# Data_Conversion_BottomBoard.net
KiCad netlist of a schematic drawn in Altium Designer
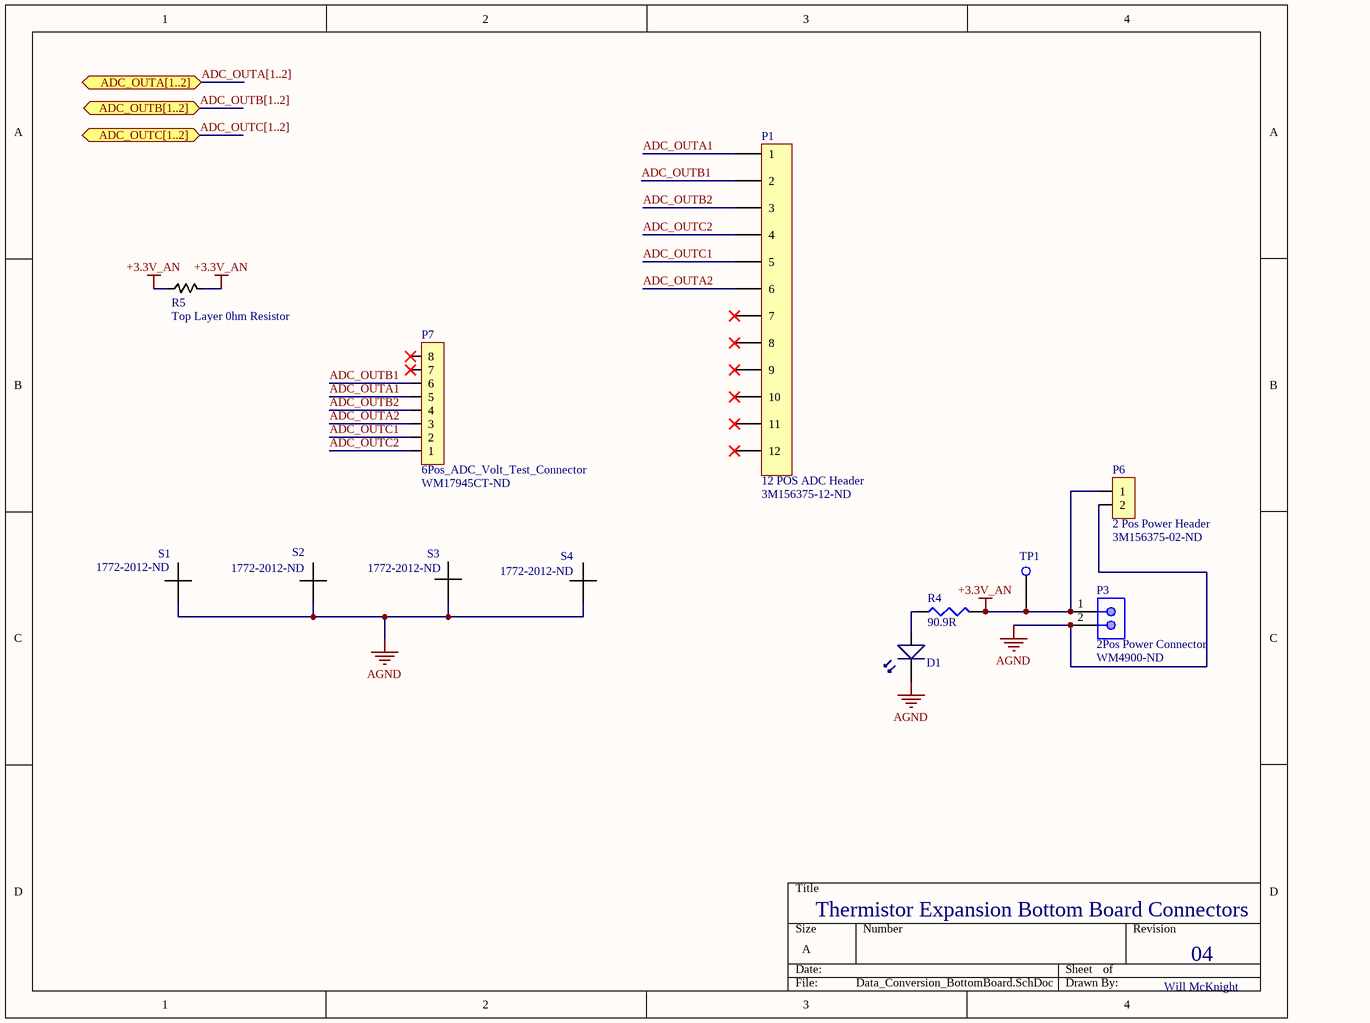
[diagram p0: Data_Conversion_BottomBoard.SchDoc]

(export (version "E")
  (design (tool "Eeschema 10.0.6"))
  (components
    (comp (ref "D1")
      (value "LED")
      (footprint "Green_SMD_LED")
      (fields
        (field (name "MANUFACTURER") "Dialight")
        (field (name "MANUFACTURER PART NUMBER") "5988070107F")
      )
      (libsource (lib "Schematic_Library") (part "GREEN_LED"))
    )
    (comp (ref "P1")
      (value "12 POS ADC Header")
      (footprint "12 POS Dual Header")
      (description "Interboard connector for thermistors connecting to ADC")
      (fields
        (field (name "MANUFACTURER") "3M")
        (field (name "MANUFACTURER PART NUMBER") "929715-06-06-EU")
        (field (name "SUPPLIER PART NUMBER 1") "3M156375-12-ND")
      )
      (libsource (lib "Schematic_Library") (part "12 POS ADC Header"))
    )
    (comp (ref "P3")
      (value "2Pos Power Connector")
      (footprint "2Pos Power Connector")
      (description "Headers & Wire Housings R/A HDR 2P low profile single")
      (fields
        (field (name "MANUFACTURER") "Molex")
        (field (name "MANUFACTURER PART NUMBER") "70553-0001")
        (field (name "SUPPLIER PART NUMBER 1") "WM4900-ND")
      )
      (libsource (lib "Schematic_Library") (part "2Pos Power Connector"))
    )
    (comp (ref "P6")
      (value "2 Pos Power Header")
      (footprint "2 POS Power Header")
      (fields
        (field (name "MANUFACTURER") "3M")
        (field (name "MANUFACTURER PART NUMBER") "929715-06-01-EU")
        (field (name "SUPPLIER PART NUMBER 1") "3M156375-02-ND")
      )
      (libsource (lib "Schematic_Library") (part "2 Pos Power Header"))
    )
    (comp (ref "P7")
      (value "6Pos_ADC_Volt_Test_Connector")
      (footprint "6POS_ADC_Volt_TEST")
      (description "Connector Header Surface Mount, Right Angle 6 position 0.079\" (2.00mm)")
      (fields
        (field (name "MANUFACTURER") "Molex")
        (field (name "MANUFACTURER PART NUMBER") "5055780671")
        (field (name "SUPPLIER PART NUMBER 1") "WM17945CT-ND")
      )
      (libsource (lib "Schematic_Library") (part "6Pos_ADC_Volt_Test_Connector"))
    )
    (comp (ref "R4")
      (value "Green")
      (footprint "Green_LED_Resistor_90.9")
      (fields
        (field (name "MANUFACTURER") "Panasonic")
        (field (name "MANUFACTURER PART NUMBER") "ERJ-1GNF90R9C")
        (field (name "TOLERANCE") "1%")
        (field (name "RESISTANCE") "90.9R")
      )
      (libsource (lib "Schematic_Library") (part "Green_LED_Res"))
    )
    (comp (ref "R5")
      (value "Top Layer 0hm Resistor")
      (footprint "Top Layer 0ohm Resistor")
      (libsource (lib "Schematic_Library") (part "Top Layer 0hm Resistor"))
    )
    (comp (ref "S1")
      (value "#6-32 Female-Male Standoff")
      (footprint "#6-32 Female-Male Standoff")
      (description "Hex Standoff Threaded #6-32 Aluminum 0.375\" (9.53mm) 3/8\"")
      (fields
        (field (name "MANUFACTURER") "RAF")
        (field (name "MANUFACTURER PART NUMBER") "4532-632-AL-7")
        (field (name "SUPPLIER PART NUMBER 1") "1772-2012-ND")
      )
      (libsource (lib "Schematic_Library") (part "#6-32 Female-Male Standoff"))
    )
    (comp (ref "S2")
      (value "#6-32 Female-Male Standoff")
      (footprint "#6-32 Female-Male Standoff")
      (description "Hex Standoff Threaded #6-32 Aluminum 0.375\" (9.53mm) 3/8\"")
      (fields
        (field (name "MANUFACTURER") "RAF")
        (field (name "MANUFACTURER PART NUMBER") "4532-632-AL-7")
        (field (name "SUPPLIER PART NUMBER 1") "1772-2012-ND")
      )
      (libsource (lib "Schematic_Library") (part "#6-32 Female-Male Standoff"))
    )
    (comp (ref "S3")
      (value "#6-32 Female-Male Standoff")
      (footprint "#6-32 Female-Male Standoff")
      (description "Hex Standoff Threaded #6-32 Aluminum 0.375\" (9.53mm) 3/8\"")
      (fields
        (field (name "MANUFACTURER") "RAF")
        (field (name "MANUFACTURER PART NUMBER") "4532-632-AL-7")
        (field (name "SUPPLIER PART NUMBER 1") "1772-2012-ND")
      )
      (libsource (lib "Schematic_Library") (part "#6-32 Female-Male Standoff"))
    )
    (comp (ref "S4")
      (value "#6-32 Female-Male Standoff")
      (footprint "#6-32 Female-Male Standoff")
      (description "Hex Standoff Threaded #6-32 Aluminum 0.375\" (9.53mm) 3/8\"")
      (fields
        (field (name "MANUFACTURER") "RAF")
        (field (name "MANUFACTURER PART NUMBER") "4532-632-AL-7")
        (field (name "SUPPLIER PART NUMBER 1") "1772-2012-ND")
      )
      (libsource (lib "Schematic_Library") (part "#6-32 Female-Male Standoff"))
    )
    (comp (ref "TP1")
      (value "Test Point")
      (footprint "Test Point")
      (libsource (lib "Schematic_Library") (part "Test Point"))
    )
  )
  (nets
    (net (code "1") (name "+3.3V_AN") (class "Default")
      (node (ref "P3") (pin "1") (pinfunction "1_1") (pintype "passive"))
      (node (ref "P6") (pin "1") (pinfunction "1_1") (pintype "passive"))
      (node (ref "R4") (pin "2") (pinfunction "2_2") (pintype "passive"))
      (node (ref "R5") (pin "1") (pinfunction "1_1") (pintype "passive"))
      (node (ref "R5") (pin "2") (pinfunction "2_2") (pintype "passive"))
      (node (ref "TP1") (pin "1") (pinfunction "1_1") (pintype "passive"))
    )
    (net (code "2") (name "/ADC_OUTA1") (class "Default")
      (node (ref "P1") (pin "1") (pinfunction "1_1") (pintype "passive"))
      (node (ref "P7") (pin "5") (pinfunction "5_5") (pintype "passive"))
    )
    (net (code "3") (name "/ADC_OUTA2") (class "Default")
      (node (ref "P1") (pin "6") (pinfunction "6_6") (pintype "passive"))
      (node (ref "P7") (pin "3") (pinfunction "3_3") (pintype "passive"))
    )
    (net (code "5") (name "/ADC_OUTB1") (class "Default")
      (node (ref "P1") (pin "2") (pinfunction "2_2") (pintype "passive"))
      (node (ref "P7") (pin "6") (pinfunction "6_6") (pintype "passive"))
    )
    (net (code "6") (name "/ADC_OUTB2") (class "Default")
      (node (ref "P1") (pin "3") (pinfunction "3_3") (pintype "passive"))
      (node (ref "P7") (pin "4") (pinfunction "4_4") (pintype "passive"))
    )
    (net (code "8") (name "/ADC_OUTC1") (class "Default")
      (node (ref "P1") (pin "5") (pinfunction "5_5") (pintype "passive"))
      (node (ref "P7") (pin "2") (pinfunction "2_2") (pintype "passive"))
    )
    (net (code "9") (name "/ADC_OUTC2") (class "Default")
      (node (ref "P1") (pin "4") (pinfunction "4_4") (pintype "passive"))
      (node (ref "P7") (pin "1") (pinfunction "1_1") (pintype "passive"))
    )
    (net (code "11") (name "AGND") (class "Default")
      (node (ref "D1") (pin "1") (pinfunction "1_1") (pintype "passive"))
      (node (ref "P3") (pin "2") (pinfunction "2_2") (pintype "passive"))
      (node (ref "P6") (pin "2") (pinfunction "2_2") (pintype "passive"))
      (node (ref "S1") (pin "1") (pinfunction "1_1") (pintype "passive"))
      (node (ref "S2") (pin "1") (pinfunction "1_1") (pintype "passive"))
      (node (ref "S3") (pin "1") (pinfunction "1_1") (pintype "passive"))
      (node (ref "S4") (pin "1") (pinfunction "1_1") (pintype "passive"))
    )
    (net (code "12") (name "Net-(D1-Pad2)") (class "Default")
      (node (ref "D1") (pin "2") (pinfunction "2_2") (pintype "passive"))
      (node (ref "R4") (pin "1") (pinfunction "1_1") (pintype "passive"))
    )
    (net (code "13") (name "unconnected-(P1-Pad7)") (class "Default")
      (node (ref "P1") (pin "7") (pinfunction "7_7") (pintype "passive+no_connect"))
    )
    (net (code "14") (name "unconnected-(P1-Pad8)") (class "Default")
      (node (ref "P1") (pin "8") (pinfunction "8_8") (pintype "passive+no_connect"))
    )
    (net (code "15") (name "unconnected-(P1-Pad9)") (class "Default")
      (node (ref "P1") (pin "9") (pinfunction "9_9") (pintype "passive+no_connect"))
    )
    (net (code "16") (name "unconnected-(P1-Pad10)") (class "Default")
      (node (ref "P1") (pin "10") (pinfunction "10_10") (pintype "passive+no_connect"))
    )
    (net (code "17") (name "unconnected-(P1-Pad11)") (class "Default")
      (node (ref "P1") (pin "11") (pinfunction "11_11") (pintype "passive+no_connect"))
    )
    (net (code "18") (name "unconnected-(P1-Pad12)") (class "Default")
      (node (ref "P1") (pin "12") (pinfunction "12_12") (pintype "passive+no_connect"))
    )
    (net (code "19") (name "unconnected-(P7-Pad7)") (class "Default")
      (node (ref "P7") (pin "7") (pinfunction "7_7") (pintype "passive+no_connect"))
    )
    (net (code "20") (name "unconnected-(P7-Pad8)") (class "Default")
      (node (ref "P7") (pin "8") (pinfunction "8_8") (pintype "passive+no_connect"))
    )
  )
)
